# 12.net
KiCad netlist of a schematic drawn in Altium Designer
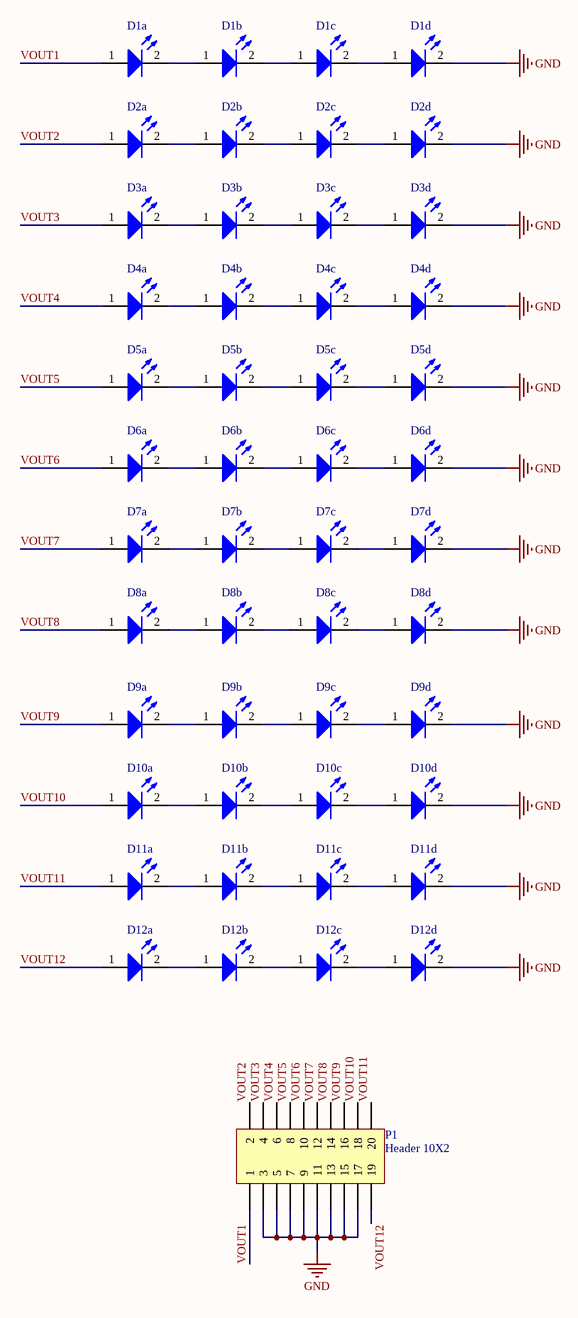
[diagram p0: 数粒机发射板12通道.SchDoc]

(export (version "E")
  (design (tool "Eeschema 10.0.6"))
  (components
    (comp (ref "D1a")
      (value "红外接收珠子")
      (footprint "EL-1KL3")
      (description "EL-1KL3")
      (fields (field (name "PUBLISHER") "Altium Limited"))
      (libsource (lib "Miscellaneous Devices") (part "EL-1KL3"))
    )
    (comp (ref "D1b")
      (value "红外接收珠子")
      (footprint "EL-1KL3")
      (description "EL-1KL3")
      (fields (field (name "PUBLISHER") "Altium Limited"))
      (libsource (lib "Miscellaneous Devices") (part "EL-1KL3"))
    )
    (comp (ref "D1c")
      (value "红外接收珠子")
      (footprint "EL-1KL3")
      (description "EL-1KL3")
      (fields (field (name "PUBLISHER") "Altium Limited"))
      (libsource (lib "Miscellaneous Devices") (part "EL-1KL3"))
    )
    (comp (ref "D1d")
      (value "红外接收珠子")
      (footprint "EL-1KL3")
      (description "EL-1KL3")
      (fields (field (name "PUBLISHER") "Altium Limited"))
      (libsource (lib "Miscellaneous Devices") (part "EL-1KL3"))
    )
    (comp (ref "D2a")
      (value "红外接收珠子")
      (footprint "EL-1KL3")
      (description "EL-1KL3")
      (fields (field (name "PUBLISHER") "Altium Limited"))
      (libsource (lib "Miscellaneous Devices") (part "EL-1KL3"))
    )
    (comp (ref "D2b")
      (value "红外接收珠子")
      (footprint "EL-1KL3")
      (description "EL-1KL3")
      (fields (field (name "PUBLISHER") "Altium Limited"))
      (libsource (lib "Miscellaneous Devices") (part "EL-1KL3"))
    )
    (comp (ref "D2c")
      (value "红外接收珠子")
      (footprint "EL-1KL3")
      (description "EL-1KL3")
      (fields (field (name "PUBLISHER") "Altium Limited"))
      (libsource (lib "Miscellaneous Devices") (part "EL-1KL3"))
    )
    (comp (ref "D2d")
      (value "红外接收珠子")
      (footprint "EL-1KL3")
      (description "EL-1KL3")
      (fields (field (name "PUBLISHER") "Altium Limited"))
      (libsource (lib "Miscellaneous Devices") (part "EL-1KL3"))
    )
    (comp (ref "D3a")
      (value "红外接收珠子")
      (footprint "EL-1KL3")
      (description "EL-1KL3")
      (fields (field (name "PUBLISHER") "Altium Limited"))
      (libsource (lib "Miscellaneous Devices") (part "EL-1KL3"))
    )
    (comp (ref "D3b")
      (value "红外接收珠子")
      (footprint "EL-1KL3")
      (description "EL-1KL3")
      (fields (field (name "PUBLISHER") "Altium Limited"))
      (libsource (lib "Miscellaneous Devices") (part "EL-1KL3"))
    )
    (comp (ref "D3c")
      (value "红外接收珠子")
      (footprint "EL-1KL3")
      (description "EL-1KL3")
      (fields (field (name "PUBLISHER") "Altium Limited"))
      (libsource (lib "Miscellaneous Devices") (part "EL-1KL3"))
    )
    (comp (ref "D3d")
      (value "红外接收珠子")
      (footprint "EL-1KL3")
      (description "EL-1KL3")
      (fields (field (name "PUBLISHER") "Altium Limited"))
      (libsource (lib "Miscellaneous Devices") (part "EL-1KL3"))
    )
    (comp (ref "D4a")
      (value "红外接收珠子")
      (footprint "EL-1KL3")
      (description "EL-1KL3")
      (fields (field (name "PUBLISHER") "Altium Limited"))
      (libsource (lib "Miscellaneous Devices") (part "EL-1KL3"))
    )
    (comp (ref "D4b")
      (value "红外接收珠子")
      (footprint "EL-1KL3")
      (description "EL-1KL3")
      (fields (field (name "PUBLISHER") "Altium Limited"))
      (libsource (lib "Miscellaneous Devices") (part "EL-1KL3"))
    )
    (comp (ref "D4c")
      (value "红外接收珠子")
      (footprint "EL-1KL3")
      (description "EL-1KL3")
      (fields (field (name "PUBLISHER") "Altium Limited"))
      (libsource (lib "Miscellaneous Devices") (part "EL-1KL3"))
    )
    (comp (ref "D4d")
      (value "红外接收珠子")
      (footprint "EL-1KL3")
      (description "EL-1KL3")
      (fields (field (name "PUBLISHER") "Altium Limited"))
      (libsource (lib "Miscellaneous Devices") (part "EL-1KL3"))
    )
    (comp (ref "D5a")
      (value "红外接收珠子")
      (footprint "EL-1KL3")
      (description "EL-1KL3")
      (fields (field (name "PUBLISHER") "Altium Limited"))
      (libsource (lib "Miscellaneous Devices") (part "EL-1KL3"))
    )
    (comp (ref "D5b")
      (value "红外接收珠子")
      (footprint "EL-1KL3")
      (description "EL-1KL3")
      (fields (field (name "PUBLISHER") "Altium Limited"))
      (libsource (lib "Miscellaneous Devices") (part "EL-1KL3"))
    )
    (comp (ref "D5c")
      (value "红外接收珠子")
      (footprint "EL-1KL3")
      (description "EL-1KL3")
      (fields (field (name "PUBLISHER") "Altium Limited"))
      (libsource (lib "Miscellaneous Devices") (part "EL-1KL3"))
    )
    (comp (ref "D5d")
      (value "红外接收珠子")
      (footprint "EL-1KL3")
      (description "EL-1KL3")
      (fields (field (name "PUBLISHER") "Altium Limited"))
      (libsource (lib "Miscellaneous Devices") (part "EL-1KL3"))
    )
    (comp (ref "D6a")
      (value "红外接收珠子")
      (footprint "EL-1KL3")
      (description "EL-1KL3")
      (fields (field (name "PUBLISHER") "Altium Limited"))
      (libsource (lib "Miscellaneous Devices") (part "EL-1KL3"))
    )
    (comp (ref "D6b")
      (value "红外接收珠子")
      (footprint "EL-1KL3")
      (description "EL-1KL3")
      (fields (field (name "PUBLISHER") "Altium Limited"))
      (libsource (lib "Miscellaneous Devices") (part "EL-1KL3"))
    )
    (comp (ref "D6c")
      (value "红外接收珠子")
      (footprint "EL-1KL3")
      (description "EL-1KL3")
      (fields (field (name "PUBLISHER") "Altium Limited"))
      (libsource (lib "Miscellaneous Devices") (part "EL-1KL3"))
    )
    (comp (ref "D6d")
      (value "红外接收珠子")
      (footprint "EL-1KL3")
      (description "EL-1KL3")
      (fields (field (name "PUBLISHER") "Altium Limited"))
      (libsource (lib "Miscellaneous Devices") (part "EL-1KL3"))
    )
    (comp (ref "D7a")
      (value "红外接收珠子")
      (footprint "EL-1KL3")
      (description "EL-1KL3")
      (fields (field (name "PUBLISHER") "Altium Limited"))
      (libsource (lib "Miscellaneous Devices") (part "EL-1KL3"))
    )
    (comp (ref "D7b")
      (value "红外接收珠子")
      (footprint "EL-1KL3")
      (description "EL-1KL3")
      (fields (field (name "PUBLISHER") "Altium Limited"))
      (libsource (lib "Miscellaneous Devices") (part "EL-1KL3"))
    )
    (comp (ref "D7c")
      (value "红外接收珠子")
      (footprint "EL-1KL3")
      (description "EL-1KL3")
      (fields (field (name "PUBLISHER") "Altium Limited"))
      (libsource (lib "Miscellaneous Devices") (part "EL-1KL3"))
    )
    (comp (ref "D7d")
      (value "红外接收珠子")
      (footprint "EL-1KL3")
      (description "EL-1KL3")
      (fields (field (name "PUBLISHER") "Altium Limited"))
      (libsource (lib "Miscellaneous Devices") (part "EL-1KL3"))
    )
    (comp (ref "D8a")
      (value "红外接收珠子")
      (footprint "EL-1KL3")
      (description "EL-1KL3")
      (fields (field (name "PUBLISHER") "Altium Limited"))
      (libsource (lib "Miscellaneous Devices") (part "EL-1KL3"))
    )
    (comp (ref "D8b")
      (value "红外接收珠子")
      (footprint "EL-1KL3")
      (description "EL-1KL3")
      (fields (field (name "PUBLISHER") "Altium Limited"))
      (libsource (lib "Miscellaneous Devices") (part "EL-1KL3"))
    )
    (comp (ref "D8c")
      (value "红外接收珠子")
      (footprint "EL-1KL3")
      (description "EL-1KL3")
      (fields (field (name "PUBLISHER") "Altium Limited"))
      (libsource (lib "Miscellaneous Devices") (part "EL-1KL3"))
    )
    (comp (ref "D8d")
      (value "红外接收珠子")
      (footprint "EL-1KL3")
      (description "EL-1KL3")
      (fields (field (name "PUBLISHER") "Altium Limited"))
      (libsource (lib "Miscellaneous Devices") (part "EL-1KL3"))
    )
    (comp (ref "D9a")
      (value "红外接收珠子")
      (footprint "EL-1KL3")
      (description "EL-1KL3")
      (fields (field (name "PUBLISHER") "Altium Limited"))
      (libsource (lib "Miscellaneous Devices") (part "EL-1KL3"))
    )
    (comp (ref "D9b")
      (value "红外接收珠子")
      (footprint "EL-1KL3")
      (description "EL-1KL3")
      (fields (field (name "PUBLISHER") "Altium Limited"))
      (libsource (lib "Miscellaneous Devices") (part "EL-1KL3"))
    )
    (comp (ref "D9c")
      (value "红外接收珠子")
      (footprint "EL-1KL3")
      (description "EL-1KL3")
      (fields (field (name "PUBLISHER") "Altium Limited"))
      (libsource (lib "Miscellaneous Devices") (part "EL-1KL3"))
    )
    (comp (ref "D9d")
      (value "红外接收珠子")
      (footprint "EL-1KL3")
      (description "EL-1KL3")
      (fields (field (name "PUBLISHER") "Altium Limited"))
      (libsource (lib "Miscellaneous Devices") (part "EL-1KL3"))
    )
    (comp (ref "D10a")
      (value "红外接收珠子")
      (footprint "EL-1KL3")
      (description "EL-1KL3")
      (fields (field (name "PUBLISHER") "Altium Limited"))
      (libsource (lib "Miscellaneous Devices") (part "EL-1KL3"))
    )
    (comp (ref "D10b")
      (value "红外接收珠子")
      (footprint "EL-1KL3")
      (description "EL-1KL3")
      (fields (field (name "PUBLISHER") "Altium Limited"))
      (libsource (lib "Miscellaneous Devices") (part "EL-1KL3"))
    )
    (comp (ref "D10c")
      (value "红外接收珠子")
      (footprint "EL-1KL3")
      (description "EL-1KL3")
      (fields (field (name "PUBLISHER") "Altium Limited"))
      (libsource (lib "Miscellaneous Devices") (part "EL-1KL3"))
    )
    (comp (ref "D10d")
      (value "红外接收珠子")
      (footprint "EL-1KL3")
      (description "EL-1KL3")
      (fields (field (name "PUBLISHER") "Altium Limited"))
      (libsource (lib "Miscellaneous Devices") (part "EL-1KL3"))
    )
    (comp (ref "D11a")
      (value "红外接收珠子")
      (footprint "EL-1KL3")
      (description "EL-1KL3")
      (fields (field (name "PUBLISHER") "Altium Limited"))
      (libsource (lib "Miscellaneous Devices") (part "EL-1KL3"))
    )
    (comp (ref "D11b")
      (value "红外接收珠子")
      (footprint "EL-1KL3")
      (description "EL-1KL3")
      (fields (field (name "PUBLISHER") "Altium Limited"))
      (libsource (lib "Miscellaneous Devices") (part "EL-1KL3"))
    )
    (comp (ref "D11c")
      (value "红外接收珠子")
      (footprint "EL-1KL3")
      (description "EL-1KL3")
      (fields (field (name "PUBLISHER") "Altium Limited"))
      (libsource (lib "Miscellaneous Devices") (part "EL-1KL3"))
    )
    (comp (ref "D11d")
      (value "红外接收珠子")
      (footprint "EL-1KL3")
      (description "EL-1KL3")
      (fields (field (name "PUBLISHER") "Altium Limited"))
      (libsource (lib "Miscellaneous Devices") (part "EL-1KL3"))
    )
    (comp (ref "D12a")
      (value "红外接收珠子")
      (footprint "EL-1KL3")
      (description "EL-1KL3")
      (fields (field (name "PUBLISHER") "Altium Limited"))
      (libsource (lib "Miscellaneous Devices") (part "EL-1KL3"))
    )
    (comp (ref "D12b")
      (value "红外接收珠子")
      (footprint "EL-1KL3")
      (description "EL-1KL3")
      (fields (field (name "PUBLISHER") "Altium Limited"))
      (libsource (lib "Miscellaneous Devices") (part "EL-1KL3"))
    )
    (comp (ref "D12c")
      (value "红外接收珠子")
      (footprint "EL-1KL3")
      (description "EL-1KL3")
      (fields (field (name "PUBLISHER") "Altium Limited"))
      (libsource (lib "Miscellaneous Devices") (part "EL-1KL3"))
    )
    (comp (ref "D12d")
      (value "红外接收珠子")
      (footprint "EL-1KL3")
      (description "EL-1KL3")
      (fields (field (name "PUBLISHER") "Altium Limited"))
      (libsource (lib "Miscellaneous Devices") (part "EL-1KL3"))
    )
    (comp (ref "P1")
      (value "Header 10X2")
      (footprint "niujiaocha20p")
      (description "Header, 10-Pin, Dual row")
      (fields (field (name "PUBLISHER") "Altium Limited"))
      (libsource (lib "Miscellaneous Connectors") (part "Header 10X2"))
    )
  )
  (nets
    (net (code "1") (name "/VOUT1") (class "Default")
      (node (ref "D1a") (pin "1") (pinfunction "A_1") (pintype "passive"))
      (node (ref "P1") (pin "1") (pinfunction "1_1") (pintype "passive"))
    )
    (net (code "2") (name "/VOUT2") (class "Default")
      (node (ref "D2a") (pin "1") (pinfunction "A_1") (pintype "passive"))
      (node (ref "P1") (pin "2") (pinfunction "2_2") (pintype "passive"))
    )
    (net (code "3") (name "/VOUT3") (class "Default")
      (node (ref "D3a") (pin "1") (pinfunction "A_1") (pintype "passive"))
      (node (ref "P1") (pin "4") (pinfunction "4_4") (pintype "passive"))
    )
    (net (code "4") (name "/VOUT4") (class "Default")
      (node (ref "D4a") (pin "1") (pinfunction "A_1") (pintype "passive"))
      (node (ref "P1") (pin "6") (pinfunction "6_6") (pintype "passive"))
    )
    (net (code "5") (name "/VOUT5") (class "Default")
      (node (ref "D5a") (pin "1") (pinfunction "A_1") (pintype "passive"))
      (node (ref "P1") (pin "8") (pinfunction "8_8") (pintype "passive"))
    )
    (net (code "6") (name "/VOUT6") (class "Default")
      (node (ref "D6a") (pin "1") (pinfunction "A_1") (pintype "passive"))
      (node (ref "P1") (pin "10") (pinfunction "10_10") (pintype "passive"))
    )
    (net (code "7") (name "/VOUT7") (class "Default")
      (node (ref "D7a") (pin "1") (pinfunction "A_1") (pintype "passive"))
      (node (ref "P1") (pin "12") (pinfunction "12_12") (pintype "passive"))
    )
    (net (code "8") (name "/VOUT8") (class "Default")
      (node (ref "D8a") (pin "1") (pinfunction "A_1") (pintype "passive"))
      (node (ref "P1") (pin "14") (pinfunction "14_14") (pintype "passive"))
    )
    (net (code "9") (name "/VOUT9") (class "Default")
      (node (ref "D9a") (pin "1") (pinfunction "A_1") (pintype "passive"))
      (node (ref "P1") (pin "16") (pinfunction "16_16") (pintype "passive"))
    )
    (net (code "10") (name "/VOUT10") (class "Default")
      (node (ref "D10a") (pin "1") (pinfunction "A_1") (pintype "passive"))
      (node (ref "P1") (pin "18") (pinfunction "18_18") (pintype "passive"))
    )
    (net (code "11") (name "/VOUT11") (class "Default")
      (node (ref "D11a") (pin "1") (pinfunction "A_1") (pintype "passive"))
      (node (ref "P1") (pin "20") (pinfunction "20_20") (pintype "passive"))
    )
    (net (code "12") (name "/VOUT12") (class "Default")
      (node (ref "D12a") (pin "1") (pinfunction "A_1") (pintype "passive"))
      (node (ref "P1") (pin "19") (pinfunction "19_19") (pintype "passive"))
    )
    (net (code "13") (name "GND") (class "Default")
      (node (ref "D10d") (pin "2") (pinfunction "K_2") (pintype "passive"))
      (node (ref "D11d") (pin "2") (pinfunction "K_2") (pintype "passive"))
      (node (ref "D12d") (pin "2") (pinfunction "K_2") (pintype "passive"))
      (node (ref "D1d") (pin "2") (pinfunction "K_2") (pintype "passive"))
      (node (ref "D2d") (pin "2") (pinfunction "K_2") (pintype "passive"))
      (node (ref "D3d") (pin "2") (pinfunction "K_2") (pintype "passive"))
      (node (ref "D4d") (pin "2") (pinfunction "K_2") (pintype "passive"))
      (node (ref "D5d") (pin "2") (pinfunction "K_2") (pintype "passive"))
      (node (ref "D6d") (pin "2") (pinfunction "K_2") (pintype "passive"))
      (node (ref "D7d") (pin "2") (pinfunction "K_2") (pintype "passive"))
      (node (ref "D8d") (pin "2") (pinfunction "K_2") (pintype "passive"))
      (node (ref "D9d") (pin "2") (pinfunction "K_2") (pintype "passive"))
      (node (ref "P1") (pin "11") (pinfunction "11_11") (pintype "passive"))
      (node (ref "P1") (pin "13") (pinfunction "13_13") (pintype "passive"))
      (node (ref "P1") (pin "15") (pinfunction "15_15") (pintype "passive"))
      (node (ref "P1") (pin "17") (pinfunction "17_17") (pintype "passive"))
      (node (ref "P1") (pin "3") (pinfunction "3_3") (pintype "passive"))
      (node (ref "P1") (pin "5") (pinfunction "5_5") (pintype "passive"))
      (node (ref "P1") (pin "7") (pinfunction "7_7") (pintype "passive"))
      (node (ref "P1") (pin "9") (pinfunction "9_9") (pintype "passive"))
    )
    (net (code "14") (name "Net-(D1a-K)") (class "Default")
      (node (ref "D1a") (pin "2") (pinfunction "K_2") (pintype "passive"))
      (node (ref "D1b") (pin "1") (pinfunction "A_1") (pintype "passive"))
    )
    (net (code "15") (name "Net-(D1b-K)") (class "Default")
      (node (ref "D1b") (pin "2") (pinfunction "K_2") (pintype "passive"))
      (node (ref "D1c") (pin "1") (pinfunction "A_1") (pintype "passive"))
    )
    (net (code "16") (name "Net-(D1c-K)") (class "Default")
      (node (ref "D1c") (pin "2") (pinfunction "K_2") (pintype "passive"))
      (node (ref "D1d") (pin "1") (pinfunction "A_1") (pintype "passive"))
    )
    (net (code "17") (name "Net-(D2a-K)") (class "Default")
      (node (ref "D2a") (pin "2") (pinfunction "K_2") (pintype "passive"))
      (node (ref "D2b") (pin "1") (pinfunction "A_1") (pintype "passive"))
    )
    (net (code "18") (name "Net-(D2b-K)") (class "Default")
      (node (ref "D2b") (pin "2") (pinfunction "K_2") (pintype "passive"))
      (node (ref "D2c") (pin "1") (pinfunction "A_1") (pintype "passive"))
    )
    (net (code "19") (name "Net-(D2c-K)") (class "Default")
      (node (ref "D2c") (pin "2") (pinfunction "K_2") (pintype "passive"))
      (node (ref "D2d") (pin "1") (pinfunction "A_1") (pintype "passive"))
    )
    (net (code "20") (name "Net-(D3a-K)") (class "Default")
      (node (ref "D3a") (pin "2") (pinfunction "K_2") (pintype "passive"))
      (node (ref "D3b") (pin "1") (pinfunction "A_1") (pintype "passive"))
    )
    (net (code "21") (name "Net-(D3b-K)") (class "Default")
      (node (ref "D3b") (pin "2") (pinfunction "K_2") (pintype "passive"))
      (node (ref "D3c") (pin "1") (pinfunction "A_1") (pintype "passive"))
    )
    (net (code "22") (name "Net-(D3c-K)") (class "Default")
      (node (ref "D3c") (pin "2") (pinfunction "K_2") (pintype "passive"))
      (node (ref "D3d") (pin "1") (pinfunction "A_1") (pintype "passive"))
    )
    (net (code "23") (name "Net-(D4a-K)") (class "Default")
      (node (ref "D4a") (pin "2") (pinfunction "K_2") (pintype "passive"))
      (node (ref "D4b") (pin "1") (pinfunction "A_1") (pintype "passive"))
    )
    (net (code "24") (name "Net-(D4b-K)") (class "Default")
      (node (ref "D4b") (pin "2") (pinfunction "K_2") (pintype "passive"))
      (node (ref "D4c") (pin "1") (pinfunction "A_1") (pintype "passive"))
    )
    (net (code "25") (name "Net-(D4c-K)") (class "Default")
      (node (ref "D4c") (pin "2") (pinfunction "K_2") (pintype "passive"))
      (node (ref "D4d") (pin "1") (pinfunction "A_1") (pintype "passive"))
    )
    (net (code "26") (name "Net-(D5a-K)") (class "Default")
      (node (ref "D5a") (pin "2") (pinfunction "K_2") (pintype "passive"))
      (node (ref "D5b") (pin "1") (pinfunction "A_1") (pintype "passive"))
    )
    (net (code "27") (name "Net-(D5b-K)") (class "Default")
      (node (ref "D5b") (pin "2") (pinfunction "K_2") (pintype "passive"))
      (node (ref "D5c") (pin "1") (pinfunction "A_1") (pintype "passive"))
    )
    (net (code "28") (name "Net-(D5c-K)") (class "Default")
      (node (ref "D5c") (pin "2") (pinfunction "K_2") (pintype "passive"))
      (node (ref "D5d") (pin "1") (pinfunction "A_1") (pintype "passive"))
    )
    (net (code "29") (name "Net-(D6a-K)") (class "Default")
      (node (ref "D6a") (pin "2") (pinfunction "K_2") (pintype "passive"))
      (node (ref "D6b") (pin "1") (pinfunction "A_1") (pintype "passive"))
    )
    (net (code "30") (name "Net-(D6b-K)") (class "Default")
      (node (ref "D6b") (pin "2") (pinfunction "K_2") (pintype "passive"))
      (node (ref "D6c") (pin "1") (pinfunction "A_1") (pintype "passive"))
    )
    (net (code "31") (name "Net-(D6c-K)") (class "Default")
      (node (ref "D6c") (pin "2") (pinfunction "K_2") (pintype "passive"))
      (node (ref "D6d") (pin "1") (pinfunction "A_1") (pintype "passive"))
    )
    (net (code "32") (name "Net-(D7a-K)") (class "Default")
      (node (ref "D7a") (pin "2") (pinfunction "K_2") (pintype "passive"))
      (node (ref "D7b") (pin "1") (pinfunction "A_1") (pintype "passive"))
    )
    (net (code "33") (name "Net-(D7b-K)") (class "Default")
      (node (ref "D7b") (pin "2") (pinfunction "K_2") (pintype "passive"))
      (node (ref "D7c") (pin "1") (pinfunction "A_1") (pintype "passive"))
    )
    (net (code "34") (name "Net-(D7c-K)") (class "Default")
      (node (ref "D7c") (pin "2") (pinfunction "K_2") (pintype "passive"))
      (node (ref "D7d") (pin "1") (pinfunction "A_1") (pintype "passive"))
    )
    (net (code "35") (name "Net-(D8a-K)") (class "Default")
      (node (ref "D8a") (pin "2") (pinfunction "K_2") (pintype "passive"))
      (node (ref "D8b") (pin "1") (pinfunction "A_1") (pintype "passive"))
    )
    (net (code "36") (name "Net-(D8b-K)") (class "Default")
      (node (ref "D8b") (pin "2") (pinfunction "K_2") (pintype "passive"))
      (node (ref "D8c") (pin "1") (pinfunction "A_1") (pintype "passive"))
    )
    (net (code "37") (name "Net-(D8c-K)") (class "Default")
      (node (ref "D8c") (pin "2") (pinfunction "K_2") (pintype "passive"))
      (node (ref "D8d") (pin "1") (pinfunction "A_1") (pintype "passive"))
    )
    (net (code "38") (name "Net-(D9a-K)") (class "Default")
      (node (ref "D9a") (pin "2") (pinfunction "K_2") (pintype "passive"))
      (node (ref "D9b") (pin "1") (pinfunction "A_1") (pintype "passive"))
    )
    (net (code "39") (name "Net-(D9b-K)") (class "Default")
      (node (ref "D9b") (pin "2") (pinfunction "K_2") (pintype "passive"))
      (node (ref "D9c") (pin "1") (pinfunction "A_1") (pintype "passive"))
    )
    (net (code "40") (name "Net-(D9c-K)") (class "Default")
      (node (ref "D9c") (pin "2") (pinfunction "K_2") (pintype "passive"))
      (node (ref "D9d") (pin "1") (pinfunction "A_1") (pintype "passive"))
    )
    (net (code "41") (name "Net-(D10a-K)") (class "Default")
      (node (ref "D10a") (pin "2") (pinfunction "K_2") (pintype "passive"))
      (node (ref "D10b") (pin "1") (pinfunction "A_1") (pintype "passive"))
    )
    (net (code "42") (name "Net-(D10b-K)") (class "Default")
      (node (ref "D10b") (pin "2") (pinfunction "K_2") (pintype "passive"))
      (node (ref "D10c") (pin "1") (pinfunction "A_1") (pintype "passive"))
    )
    (net (code "43") (name "Net-(D10c-K)") (class "Default")
      (node (ref "D10c") (pin "2") (pinfunction "K_2") (pintype "passive"))
      (node (ref "D10d") (pin "1") (pinfunction "A_1") (pintype "passive"))
    )
    (net (code "44") (name "Net-(D11a-K)") (class "Default")
      (node (ref "D11a") (pin "2") (pinfunction "K_2") (pintype "passive"))
      (node (ref "D11b") (pin "1") (pinfunction "A_1") (pintype "passive"))
    )
    (net (code "45") (name "Net-(D11b-K)") (class "Default")
      (node (ref "D11b") (pin "2") (pinfunction "K_2") (pintype "passive"))
      (node (ref "D11c") (pin "1") (pinfunction "A_1") (pintype "passive"))
    )
    (net (code "46") (name "Net-(D11c-K)") (class "Default")
      (node (ref "D11c") (pin "2") (pinfunction "K_2") (pintype "passive"))
      (node (ref "D11d") (pin "1") (pinfunction "A_1") (pintype "passive"))
    )
    (net (code "47") (name "Net-(D12a-K)") (class "Default")
      (node (ref "D12a") (pin "2") (pinfunction "K_2") (pintype "passive"))
      (node (ref "D12b") (pin "1") (pinfunction "A_1") (pintype "passive"))
    )
    (net (code "48") (name "Net-(D12b-K)") (class "Default")
      (node (ref "D12b") (pin "2") (pinfunction "K_2") (pintype "passive"))
      (node (ref "D12c") (pin "1") (pinfunction "A_1") (pintype "passive"))
    )
    (net (code "49") (name "Net-(D12c-K)") (class "Default")
      (node (ref "D12c") (pin "2") (pinfunction "K_2") (pintype "passive"))
      (node (ref "D12d") (pin "1") (pinfunction "A_1") (pintype "passive"))
    )
  )
)
